# power-ctl.net
KiCad netlist of a schematic drawn in EAGLE
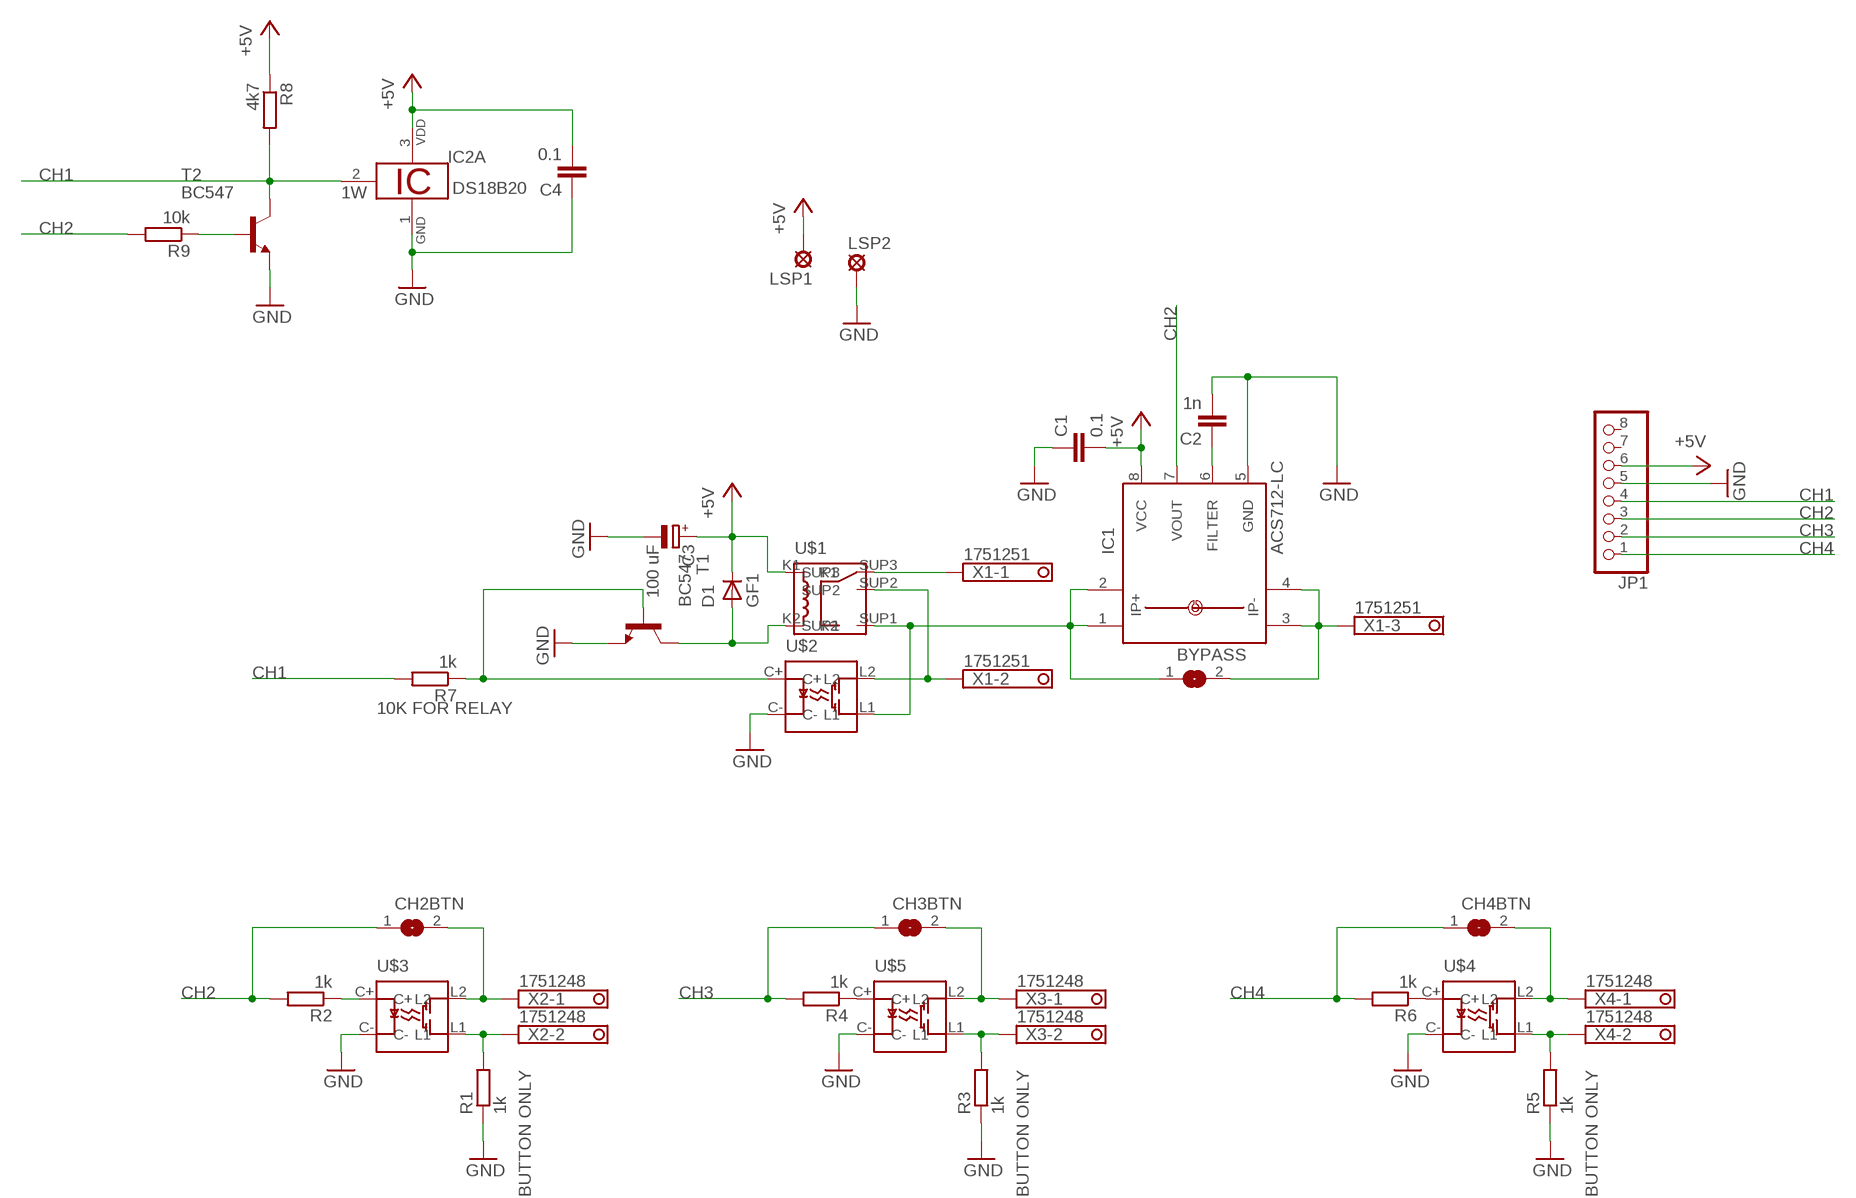
[diagram p0: schematic, sheet 1]

(export (version "E")
  (design (tool "Eeschema 10.0.6"))
  (components
    (comp (ref "BYPASS")
      (value "SJ")
      (footprint "eagle-import:SJ")
      (libsource (lib "eagle-import") (part "SJ"))
    )
    (comp (ref "C1")
      (value "0.1")
      (footprint "eagle-import:C0805")
      (libsource (lib "eagle-import") (part "C-EUC0805"))
    )
    (comp (ref "C2")
      (value "1n")
      (footprint "eagle-import:C0805")
      (libsource (lib "eagle-import") (part "C-EUC0805"))
    )
    (comp (ref "C3")
      (value "100 uF")
      (footprint "eagle-import:E2-4")
      (libsource (lib "eagle-import") (part "CPOL-EUE2-4"))
    )
    (comp (ref "C4")
      (value "0.1")
      (footprint "eagle-import:C0805")
      (libsource (lib "eagle-import") (part "C-EUC0805"))
    )
    (comp (ref "CH2BTN")
      (value "SJ")
      (footprint "eagle-import:SJ")
      (libsource (lib "eagle-import") (part "SJ"))
    )
    (comp (ref "CH3BTN")
      (value "SJ")
      (footprint "eagle-import:SJ")
      (libsource (lib "eagle-import") (part "SJ"))
    )
    (comp (ref "CH4BTN")
      (value "SJ")
      (footprint "eagle-import:SJ")
      (libsource (lib "eagle-import") (part "SJ"))
    )
    (comp (ref "D1")
      (value "GF1")
      (footprint "eagle-import:SMA-DO214AC")
      (libsource (lib "eagle-import") (part "GF1"))
    )
    (comp (ref "IC1")
      (value "ACS712-LC")
      (footprint "eagle-import:SOIC8")
      (libsource (lib "eagle-import") (part "ACS712-LC"))
    )
    (comp (ref "IC2")
      (value "DS18B20")
      (footprint "eagle-import:TO92-")
      (libsource (lib "eagle-import") (part "DS18B20"))
    )
    (comp (ref "JP1")
      (value "PINHD-1X8/90")
      (footprint "eagle-import:1X08_90")
      (libsource (lib "eagle-import") (part "PINHD-1X8/90"))
    )
    (comp (ref "LSP1")
      (value "LSP10")
      (footprint "eagle-import:LSP10")
      (libsource (lib "eagle-import") (part "LSP10"))
    )
    (comp (ref "LSP2")
      (value "LSP10")
      (footprint "eagle-import:LSP10")
      (libsource (lib "eagle-import") (part "LSP10"))
    )
    (comp (ref "R1")
      (value "1k")
      (footprint "eagle-import:M0805")
      (libsource (lib "eagle-import") (part "R-EU_M0805"))
    )
    (comp (ref "R2")
      (value "1k")
      (footprint "eagle-import:M0805")
      (libsource (lib "eagle-import") (part "R-EU_M0805"))
    )
    (comp (ref "R3")
      (value "1k")
      (footprint "eagle-import:M0805")
      (libsource (lib "eagle-import") (part "R-EU_M0805"))
    )
    (comp (ref "R4")
      (value "1k")
      (footprint "eagle-import:M0805")
      (libsource (lib "eagle-import") (part "R-EU_M0805"))
    )
    (comp (ref "R5")
      (value "1k")
      (footprint "eagle-import:M0805")
      (libsource (lib "eagle-import") (part "R-EU_M0805"))
    )
    (comp (ref "R6")
      (value "1k")
      (footprint "eagle-import:M0805")
      (libsource (lib "eagle-import") (part "R-EU_M0805"))
    )
    (comp (ref "R7")
      (value "1k")
      (footprint "eagle-import:M0805")
      (libsource (lib "eagle-import") (part "R-EU_M0805"))
    )
    (comp (ref "R8")
      (value "4k7")
      (footprint "eagle-import:M0805")
      (libsource (lib "eagle-import") (part "R-EU_M0805"))
    )
    (comp (ref "R9")
      (value "10k")
      (footprint "eagle-import:M0805")
      (libsource (lib "eagle-import") (part "R-EU_M0805"))
    )
    (comp (ref "T1")
      (value "BC547")
      (footprint "eagle-import:TO92")
      (libsource (lib "eagle-import") (part "BC547"))
    )
    (comp (ref "T2")
      (value "BC547")
      (footprint "eagle-import:TO92")
      (libsource (lib "eagle-import") (part "BC547"))
    )
    (comp (ref "U$1")
      (value "TRV-5VDC-SC-CD")
      (footprint "eagle-import:TRV-5VDC-SC-CD")
      (libsource (lib "eagle-import") (part "TRV-5VDC-SC-CD"))
    )
    (comp (ref "U$2")
      (value "CPC1030N")
      (footprint "eagle-import:SOP4")
      (libsource (lib "eagle-import") (part "CPC1030N"))
    )
    (comp (ref "U$3")
      (value "CPC1030N")
      (footprint "eagle-import:SOP4")
      (libsource (lib "eagle-import") (part "CPC1030N"))
    )
    (comp (ref "U$4")
      (value "CPC1030N")
      (footprint "eagle-import:SOP4")
      (libsource (lib "eagle-import") (part "CPC1030N"))
    )
    (comp (ref "U$5")
      (value "CPC1030N")
      (footprint "eagle-import:SOP4")
      (libsource (lib "eagle-import") (part "CPC1030N"))
    )
    (comp (ref "X1")
      (value "1751251")
      (footprint "eagle-import:1751251")
      (libsource (lib "eagle-import") (part "1751251"))
    )
    (comp (ref "X2")
      (value "1751248")
      (footprint "eagle-import:1751248")
      (libsource (lib "eagle-import") (part "1751248"))
    )
    (comp (ref "X3")
      (value "1751248")
      (footprint "eagle-import:1751248")
      (libsource (lib "eagle-import") (part "1751248"))
    )
    (comp (ref "X4")
      (value "1751248")
      (footprint "eagle-import:1751248")
      (libsource (lib "eagle-import") (part "1751248"))
    )
  )
  (nets
    (net (code "1") (name "+5V") (class "Default")
      (node (ref "C1") (pin "2") (pinfunction "2_2") (pintype "passive"))
      (node (ref "C3") (pin "+") (pinfunction "+_+") (pintype "passive"))
      (node (ref "C4") (pin "2") (pinfunction "2_2") (pintype "passive"))
      (node (ref "D1") (pin "K") (pinfunction "C_K") (pintype "passive"))
      (node (ref "IC1") (pin "8") (pinfunction "VCC_8") (pintype "power_in"))
      (node (ref "IC2") (pin "3") (pinfunction "VDD_3") (pintype "power_in"))
      (node (ref "JP1") (pin "6") (pinfunction "6_6") (pintype "passive"))
      (node (ref "LSP1") (pin "MP") (pinfunction "MP_MP") (pintype "passive"))
      (node (ref "R8") (pin "1") (pinfunction "1_1") (pintype "passive"))
      (node (ref "U$1") (pin "K1") (pinfunction "K1_K1") (pintype "bidirectional"))
    )
    (net (code "2") (name "/CH1") (class "Default")
      (node (ref "IC2") (pin "2") (pinfunction "1W_2") (pintype "power_in"))
      (node (ref "JP1") (pin "4") (pinfunction "4_4") (pintype "passive"))
      (node (ref "R7") (pin "2") (pinfunction "2_2") (pintype "passive"))
      (node (ref "R8") (pin "2") (pinfunction "2_2") (pintype "passive"))
      (node (ref "T2") (pin "3") (pinfunction "C_3") (pintype "passive"))
    )
    (net (code "3") (name "/CH2") (class "Default")
      (node (ref "CH2BTN") (pin "1") (pinfunction "1_1") (pintype "passive"))
      (node (ref "IC1") (pin "7") (pinfunction "VOUT_7") (pintype "output"))
      (node (ref "JP1") (pin "3") (pinfunction "3_3") (pintype "passive"))
      (node (ref "R2") (pin "2") (pinfunction "2_2") (pintype "passive"))
      (node (ref "R9") (pin "2") (pinfunction "2_2") (pintype "passive"))
    )
    (net (code "4") (name "/CH3") (class "Default")
      (node (ref "CH3BTN") (pin "1") (pinfunction "1_1") (pintype "passive"))
      (node (ref "JP1") (pin "2") (pinfunction "2_2") (pintype "passive"))
      (node (ref "R4") (pin "2") (pinfunction "2_2") (pintype "passive"))
    )
    (net (code "5") (name "/CH4") (class "Default")
      (node (ref "CH4BTN") (pin "1") (pinfunction "1_1") (pintype "passive"))
      (node (ref "JP1") (pin "1") (pinfunction "1_1") (pintype "passive"))
      (node (ref "R6") (pin "2") (pinfunction "2_2") (pintype "passive"))
    )
    (net (code "6") (name "GND") (class "Default")
      (node (ref "C1") (pin "1") (pinfunction "1_1") (pintype "passive"))
      (node (ref "C2") (pin "2") (pinfunction "2_2") (pintype "passive"))
      (node (ref "C3") (pin "-") (pinfunction "-_-") (pintype "passive"))
      (node (ref "C4") (pin "1") (pinfunction "1_1") (pintype "passive"))
      (node (ref "IC1") (pin "5") (pinfunction "GND_5") (pintype "power_in"))
      (node (ref "IC2") (pin "1") (pinfunction "GND_1") (pintype "power_in"))
      (node (ref "JP1") (pin "5") (pinfunction "5_5") (pintype "passive"))
      (node (ref "LSP2") (pin "MP") (pinfunction "MP_MP") (pintype "passive"))
      (node (ref "R1") (pin "1") (pinfunction "1_1") (pintype "passive"))
      (node (ref "R3") (pin "1") (pinfunction "1_1") (pintype "passive"))
      (node (ref "R5") (pin "1") (pinfunction "1_1") (pintype "passive"))
      (node (ref "T1") (pin "1") (pinfunction "E_1") (pintype "passive"))
      (node (ref "T2") (pin "1") (pinfunction "E_1") (pintype "passive"))
      (node (ref "U$2") (pin "C-") (pinfunction "C-_C-") (pintype "bidirectional"))
      (node (ref "U$3") (pin "C-") (pinfunction "C-_C-") (pintype "bidirectional"))
      (node (ref "U$4") (pin "C-") (pinfunction "C-_C-") (pintype "bidirectional"))
      (node (ref "U$5") (pin "C-") (pinfunction "C-_C-") (pintype "bidirectional"))
    )
    (net (code "7") (name "Net-(IC1-FILTER)") (class "Default")
      (node (ref "C2") (pin "1") (pinfunction "1_1") (pintype "passive"))
      (node (ref "IC1") (pin "6") (pinfunction "FILTER_6") (pintype "bidirectional"))
    )
    (net (code "8") (name "Net-(IC1-IP+)") (class "Default")
      (node (ref "BYPASS") (pin "1") (pinfunction "1_1") (pintype "passive"))
      (node (ref "IC1") (pin "1") (pinfunction "IP+_1") (pintype "passive"))
      (node (ref "IC1") (pin "2") (pinfunction "IP+1_2") (pintype "passive"))
      (node (ref "U$1") (pin "SUP1") (pinfunction "SUP1_SUP1") (pintype "bidirectional"))
      (node (ref "U$2") (pin "L1") (pinfunction "L1_L1") (pintype "bidirectional"))
    )
    (net (code "9") (name "Net-(IC1-IP-)") (class "Default")
      (node (ref "BYPASS") (pin "2") (pinfunction "2_2") (pintype "passive"))
      (node (ref "IC1") (pin "3") (pinfunction "IP-_3") (pintype "passive"))
      (node (ref "IC1") (pin "4") (pinfunction "IP-1_4") (pintype "passive"))
      (node (ref "X1") (pin "3") (pinfunction "K_3") (pintype "passive"))
    )
    (net (code "10") (name "Net-(R2-Pad1)") (class "Default")
      (node (ref "R2") (pin "1") (pinfunction "1_1") (pintype "passive"))
      (node (ref "U$3") (pin "C+") (pinfunction "C+_C+") (pintype "bidirectional"))
    )
    (net (code "11") (name "Net-(R4-Pad1)") (class "Default")
      (node (ref "R4") (pin "1") (pinfunction "1_1") (pintype "passive"))
      (node (ref "U$5") (pin "C+") (pinfunction "C+_C+") (pintype "bidirectional"))
    )
    (net (code "12") (name "Net-(R6-Pad1)") (class "Default")
      (node (ref "R6") (pin "1") (pinfunction "1_1") (pintype "passive"))
      (node (ref "U$4") (pin "C+") (pinfunction "C+_C+") (pintype "bidirectional"))
    )
    (net (code "13") (name "Net-(T1-B)") (class "Default")
      (node (ref "R7") (pin "1") (pinfunction "1_1") (pintype "passive"))
      (node (ref "T1") (pin "2") (pinfunction "B_2") (pintype "passive"))
      (node (ref "U$2") (pin "C+") (pinfunction "C+_C+") (pintype "bidirectional"))
    )
    (net (code "14") (name "Net-(T1-C)") (class "Default")
      (node (ref "D1") (pin "A") (pinfunction "A_A") (pintype "passive"))
      (node (ref "T1") (pin "3") (pinfunction "C_3") (pintype "passive"))
      (node (ref "U$1") (pin "K2") (pinfunction "K2_K2") (pintype "bidirectional"))
    )
    (net (code "15") (name "Net-(T2-B)") (class "Default")
      (node (ref "R9") (pin "1") (pinfunction "1_1") (pintype "passive"))
      (node (ref "T2") (pin "2") (pinfunction "B_2") (pintype "passive"))
    )
    (net (code "16") (name "Net-(X1A-K)") (class "Default")
      (node (ref "U$1") (pin "SUP3") (pinfunction "SUP3_SUP3") (pintype "bidirectional"))
      (node (ref "X1") (pin "1") (pinfunction "K_1") (pintype "passive"))
    )
    (net (code "17") (name "Net-(X1B-K)") (class "Default")
      (node (ref "U$1") (pin "SUP2") (pinfunction "SUP2_SUP2") (pintype "bidirectional"))
      (node (ref "U$2") (pin "L2") (pinfunction "L2_L2") (pintype "bidirectional"))
      (node (ref "X1") (pin "2") (pinfunction "K_2") (pintype "passive"))
    )
    (net (code "18") (name "Net-(X2A-K)") (class "Default")
      (node (ref "CH2BTN") (pin "2") (pinfunction "2_2") (pintype "passive"))
      (node (ref "U$3") (pin "L2") (pinfunction "L2_L2") (pintype "bidirectional"))
      (node (ref "X2") (pin "1") (pinfunction "K_1") (pintype "passive"))
    )
    (net (code "19") (name "Net-(X2B-K)") (class "Default")
      (node (ref "R1") (pin "2") (pinfunction "2_2") (pintype "passive"))
      (node (ref "U$3") (pin "L1") (pinfunction "L1_L1") (pintype "bidirectional"))
      (node (ref "X2") (pin "2") (pinfunction "K_2") (pintype "passive"))
    )
    (net (code "20") (name "Net-(X3A-K)") (class "Default")
      (node (ref "CH3BTN") (pin "2") (pinfunction "2_2") (pintype "passive"))
      (node (ref "U$5") (pin "L2") (pinfunction "L2_L2") (pintype "bidirectional"))
      (node (ref "X3") (pin "1") (pinfunction "K_1") (pintype "passive"))
    )
    (net (code "21") (name "Net-(X3B-K)") (class "Default")
      (node (ref "R3") (pin "2") (pinfunction "2_2") (pintype "passive"))
      (node (ref "U$5") (pin "L1") (pinfunction "L1_L1") (pintype "bidirectional"))
      (node (ref "X3") (pin "2") (pinfunction "K_2") (pintype "passive"))
    )
    (net (code "22") (name "Net-(X4A-K)") (class "Default")
      (node (ref "CH4BTN") (pin "2") (pinfunction "2_2") (pintype "passive"))
      (node (ref "U$4") (pin "L2") (pinfunction "L2_L2") (pintype "bidirectional"))
      (node (ref "X4") (pin "1") (pinfunction "K_1") (pintype "passive"))
    )
    (net (code "23") (name "Net-(X4B-K)") (class "Default")
      (node (ref "R5") (pin "2") (pinfunction "2_2") (pintype "passive"))
      (node (ref "U$4") (pin "L1") (pinfunction "L1_L1") (pintype "bidirectional"))
      (node (ref "X4") (pin "2") (pinfunction "K_2") (pintype "passive"))
    )
    (net (code "24") (name "unconnected-(JP1-Pad7)") (class "Default")
      (node (ref "JP1") (pin "7") (pinfunction "7_7") (pintype "passive"))
    )
    (net (code "25") (name "unconnected-(JP1-Pad8)") (class "Default")
      (node (ref "JP1") (pin "8") (pinfunction "8_8") (pintype "passive"))
    )
  )
)
